# Gator_rtc.net
KiCad netlist of a schematic drawn in EAGLE
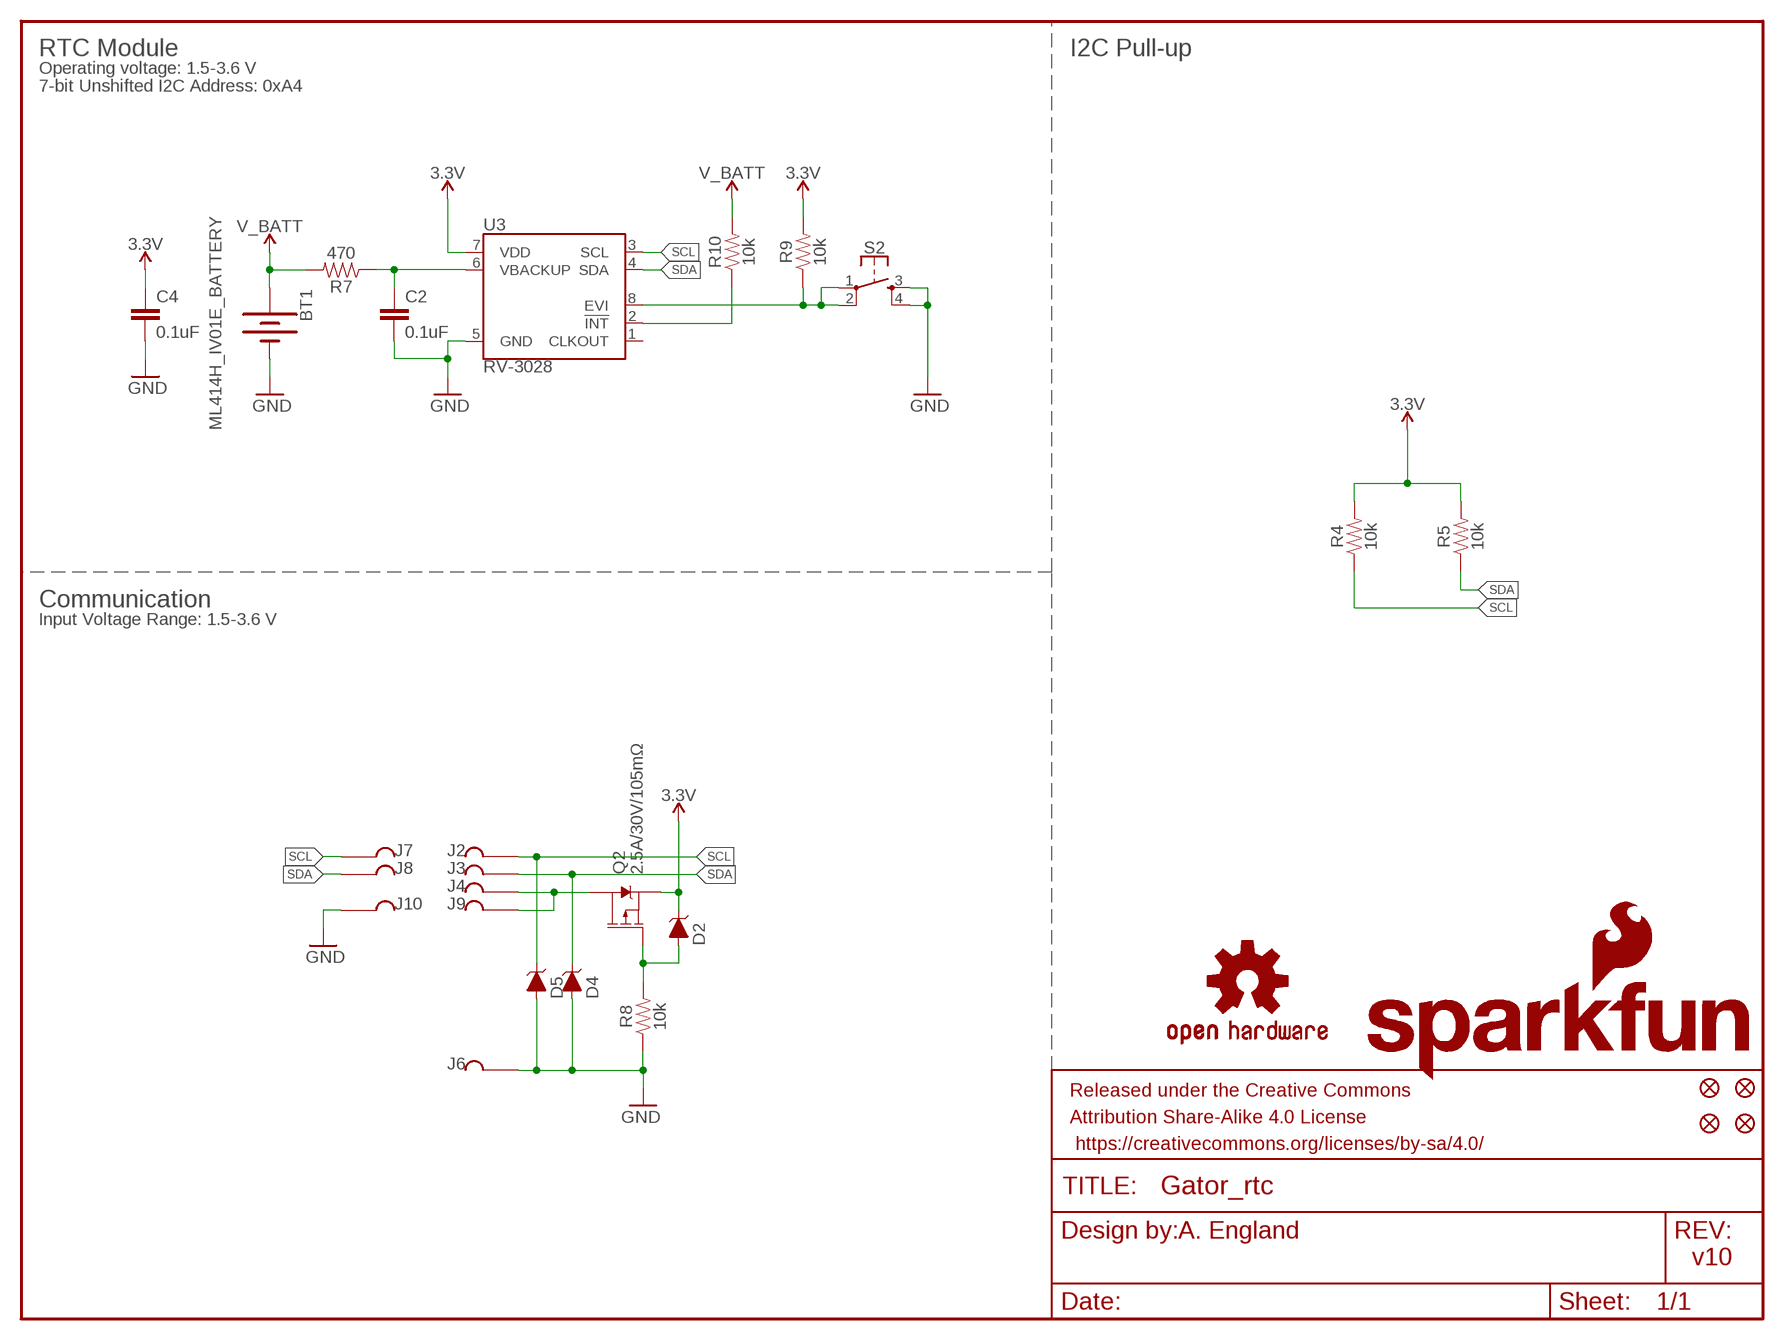
[diagram p0: schematic, sheet 1]

(export (version "E")
  (design (tool "Eeschema 10.0.6"))
  (components
    (comp (ref "BT1")
      (value "ML414H_IV01E_BATTERY")
      (footprint "eagle-import:ML414H_IV01E")
      (libsource (lib "eagle-import") (part "ML414H_IV01E_BATTERY"))
    )
    (comp (ref "C2")
      (value "0.1uF")
      (footprint "eagle-import:0603")
      (libsource (lib "eagle-import") (part "0.1UF-0603-25V-(+80/-20%)"))
    )
    (comp (ref "C4")
      (value "0.1uF")
      (footprint "eagle-import:0603")
      (libsource (lib "eagle-import") (part "0.1UF-0603-25V-(+80/-20%)"))
    )
    (comp (ref "D2")
      (value "3.6V")
      (footprint "eagle-import:SOD-323")
      (libsource (lib "eagle-import") (part "DIODE-ZENER-BZT52C3V6S"))
    )
    (comp (ref "D4")
      (value "3.6V")
      (footprint "eagle-import:SOD-323")
      (libsource (lib "eagle-import") (part "DIODE-ZENER-BZT52C3V6S"))
    )
    (comp (ref "D5")
      (value "3.6V")
      (footprint "eagle-import:SOD-323")
      (libsource (lib "eagle-import") (part "DIODE-ZENER-BZT52C3V6S"))
    )
    (comp (ref "FID1")
      (value "FIDUCIALUFIDUCIAL")
      (footprint "eagle-import:FIDUCIAL-MICRO")
      (libsource (lib "eagle-import") (part "FIDUCIALUFIDUCIAL"))
    )
    (comp (ref "FID2")
      (value "FIDUCIALUFIDUCIAL")
      (footprint "eagle-import:FIDUCIAL-MICRO")
      (libsource (lib "eagle-import") (part "FIDUCIALUFIDUCIAL"))
    )
    (comp (ref "FID3")
      (value "FIDUCIALUFIDUCIAL")
      (footprint "eagle-import:FIDUCIAL-MICRO")
      (libsource (lib "eagle-import") (part "FIDUCIALUFIDUCIAL"))
    )
    (comp (ref "FID4")
      (value "FIDUCIALUFIDUCIAL")
      (footprint "eagle-import:FIDUCIAL-MICRO")
      (libsource (lib "eagle-import") (part "FIDUCIALUFIDUCIAL"))
    )
    (comp (ref "FRAME1")
      (value "FRAME-LETTER")
      (footprint "eagle-import:CREATIVE_COMMONS")
      (libsource (lib "eagle-import") (part "FRAME-LETTER"))
    )
    (comp (ref "J2")
      (value "GATORGATOR_MINI")
      (footprint "eagle-import:GATOR_MINI")
      (libsource (lib "eagle-import") (part "GATORGATOR_MINI"))
    )
    (comp (ref "J3")
      (value "GATORGATOR_MINI")
      (footprint "eagle-import:GATOR_MINI")
      (libsource (lib "eagle-import") (part "GATORGATOR_MINI"))
    )
    (comp (ref "J4")
      (value "GATORGATOR_MINI")
      (footprint "eagle-import:GATOR_MINI")
      (libsource (lib "eagle-import") (part "GATORGATOR_MINI"))
    )
    (comp (ref "J6")
      (value "GATORGATOR_MINI")
      (footprint "eagle-import:GATOR_MINI")
      (libsource (lib "eagle-import") (part "GATORGATOR_MINI"))
    )
    (comp (ref "J7")
      (value "GATORGATOR_MINI")
      (footprint "eagle-import:GATOR_MINI")
      (libsource (lib "eagle-import") (part "GATORGATOR_MINI"))
    )
    (comp (ref "J8")
      (value "GATORGATOR_MINI")
      (footprint "eagle-import:GATOR_MINI")
      (libsource (lib "eagle-import") (part "GATORGATOR_MINI"))
    )
    (comp (ref "J9")
      (value "GATORGATOR_MINI")
      (footprint "eagle-import:GATOR_MINI")
      (libsource (lib "eagle-import") (part "GATORGATOR_MINI"))
    )
    (comp (ref "J10")
      (value "GATORGATOR_MINI")
      (footprint "eagle-import:GATOR_MINI")
      (libsource (lib "eagle-import") (part "GATORGATOR_MINI"))
    )
    (comp (ref "LOGO2")
      (value "OSHW-LOGOMINI")
      (footprint "eagle-import:OSHW-LOGO-MINI")
      (libsource (lib "eagle-import") (part "OSHW-LOGOMINI"))
    )
    (comp (ref "LOGO4")
      (value "SFE_LOGO_NAME_FLAME.1_INCH")
      (footprint "eagle-import:SFE_LOGO_NAME_FLAME_.1")
      (libsource (lib "eagle-import") (part "SFE_LOGO_NAME_FLAME.1_INCH"))
    )
    (comp (ref "Q2")
      (value "2.5A/30V/105mΩ")
      (footprint "eagle-import:SOT23-3")
      (libsource (lib "eagle-import") (part "MOSFET_PCH-DMG2307L"))
    )
    (comp (ref "R4")
      (value "10k")
      (footprint "eagle-import:0603")
      (libsource (lib "eagle-import") (part "10KOHM-0603-1/10W-1%"))
    )
    (comp (ref "R5")
      (value "10k")
      (footprint "eagle-import:0603")
      (libsource (lib "eagle-import") (part "10KOHM-0603-1/10W-1%"))
    )
    (comp (ref "R7")
      (value "470")
      (footprint "eagle-import:0603")
      (libsource (lib "eagle-import") (part "470OHM-0603-1/10W-1%"))
    )
    (comp (ref "R8")
      (value "10k")
      (footprint "eagle-import:0603")
      (libsource (lib "eagle-import") (part "10KOHM-0603-1/10W-1%"))
    )
    (comp (ref "R9")
      (value "10k")
      (footprint "eagle-import:0603")
      (libsource (lib "eagle-import") (part "10KOHM-0603-1/10W-1%"))
    )
    (comp (ref "R10")
      (value "10k")
      (footprint "eagle-import:0603")
      (libsource (lib "eagle-import") (part "10KOHM-0603-1/10W-1%"))
    )
    (comp (ref "S2")
      (value "MOMENTARY-SWITCH-SPST-2-SMD-5.2MM-TALL")
      (footprint "eagle-import:TACTILE_SWITCH_SMD_5.2MM")
      (libsource (lib "eagle-import") (part "MOMENTARY-SWITCH-SPST-2-SMD-5.2MM-TALL"))
    )
    (comp (ref "U3")
      (value "RV-3028")
      (footprint "eagle-import:RV-3028")
      (libsource (lib "eagle-import") (part "RV-3028"))
    )
  )
  (nets
    (net (code "1") (name "3.3V") (class "Default")
      (node (ref "C4") (pin "1") (pinfunction "1_1") (pintype "passive"))
      (node (ref "D2") (pin "C") (pinfunction "C_C") (pintype "passive"))
      (node (ref "Q2") (pin "2") (pinfunction "S_2") (pintype "bidirectional"))
      (node (ref "R4") (pin "2") (pinfunction "2_2") (pintype "passive"))
      (node (ref "R5") (pin "2") (pinfunction "2_2") (pintype "passive"))
      (node (ref "R9") (pin "2") (pinfunction "2_2") (pintype "passive"))
      (node (ref "U3") (pin "7") (pinfunction "VDD_7") (pintype "bidirectional"))
    )
    (net (code "2") (name "GND") (class "Default")
      (node (ref "BT1") (pin "-") (pinfunction "-_-") (pintype "power_in"))
      (node (ref "C2") (pin "2") (pinfunction "2_2") (pintype "passive"))
      (node (ref "C4") (pin "2") (pinfunction "2_2") (pintype "passive"))
      (node (ref "D4") (pin "A") (pinfunction "A_A") (pintype "passive"))
      (node (ref "D5") (pin "A") (pinfunction "A_A") (pintype "passive"))
      (node (ref "J10") (pin "P$2") (pinfunction "P$1_P$2") (pintype "bidirectional"))
      (node (ref "J6") (pin "P$2") (pinfunction "P$1_P$2") (pintype "bidirectional"))
      (node (ref "R8") (pin "1") (pinfunction "1_1") (pintype "passive"))
      (node (ref "S2") (pin "3") (pinfunction "3_3") (pintype "passive"))
      (node (ref "S2") (pin "4") (pinfunction "4_4") (pintype "passive"))
      (node (ref "U3") (pin "5") (pinfunction "GND_5") (pintype "bidirectional"))
    )
    (net (code "3") (name "Net-(J4-P$1)") (class "Default")
      (node (ref "J4") (pin "P$2") (pinfunction "P$1_P$2") (pintype "bidirectional"))
      (node (ref "J9") (pin "P$2") (pinfunction "P$1_P$2") (pintype "bidirectional"))
      (node (ref "Q2") (pin "3") (pinfunction "D_3") (pintype "bidirectional"))
    )
    (net (code "4") (name "Net-(Q2-G)") (class "Default")
      (node (ref "D2") (pin "A") (pinfunction "A_A") (pintype "passive"))
      (node (ref "Q2") (pin "1") (pinfunction "G_1") (pintype "bidirectional"))
      (node (ref "R8") (pin "2") (pinfunction "2_2") (pintype "passive"))
    )
    (net (code "5") (name "Net-(U3-EVI)") (class "Default")
      (node (ref "R9") (pin "1") (pinfunction "1_1") (pintype "passive"))
      (node (ref "S2") (pin "1") (pinfunction "1_1") (pintype "passive"))
      (node (ref "S2") (pin "2") (pinfunction "2_2") (pintype "passive"))
      (node (ref "U3") (pin "8") (pinfunction "EVI_8") (pintype "bidirectional"))
    )
    (net (code "6") (name "Net-(U3-VBACKUP)") (class "Default")
      (node (ref "C2") (pin "1") (pinfunction "1_1") (pintype "passive"))
      (node (ref "R7") (pin "1") (pinfunction "1_1") (pintype "passive"))
      (node (ref "U3") (pin "6") (pinfunction "VBACKUP_6") (pintype "bidirectional"))
    )
    (net (code "7") (name "Net-(U3-~{INT})") (class "Default")
      (node (ref "R10") (pin "1") (pinfunction "1_1") (pintype "passive"))
      (node (ref "U3") (pin "2") (pinfunction "~{INT}_2") (pintype "bidirectional"))
    )
    (net (code "8") (name "SCL") (class "Default")
      (node (ref "D5") (pin "C") (pinfunction "C_C") (pintype "passive"))
      (node (ref "J2") (pin "P$2") (pinfunction "P$1_P$2") (pintype "bidirectional"))
      (node (ref "J7") (pin "P$2") (pinfunction "P$1_P$2") (pintype "bidirectional"))
      (node (ref "R4") (pin "1") (pinfunction "1_1") (pintype "passive"))
      (node (ref "U3") (pin "3") (pinfunction "SCL_3") (pintype "bidirectional"))
    )
    (net (code "9") (name "SDA") (class "Default")
      (node (ref "D4") (pin "C") (pinfunction "C_C") (pintype "passive"))
      (node (ref "J3") (pin "P$2") (pinfunction "P$1_P$2") (pintype "bidirectional"))
      (node (ref "J8") (pin "P$2") (pinfunction "P$1_P$2") (pintype "bidirectional"))
      (node (ref "R5") (pin "1") (pinfunction "1_1") (pintype "passive"))
      (node (ref "U3") (pin "4") (pinfunction "SDA_4") (pintype "bidirectional"))
    )
    (net (code "10") (name "V_BATT") (class "Default")
      (node (ref "BT1") (pin "+") (pinfunction "+_+") (pintype "power_in"))
      (node (ref "R10") (pin "2") (pinfunction "2_2") (pintype "passive"))
      (node (ref "R7") (pin "2") (pinfunction "2_2") (pintype "passive"))
    )
    (net (code "11") (name "unconnected-(U3-CLKOUT-Pad1)") (class "Default")
      (node (ref "U3") (pin "1") (pinfunction "CLKOUT_1") (pintype "bidirectional"))
    )
  )
)
